# MCISO-S05-V00-CANIsolation.net
KiCad netlist of a schematic drawn in Altium Designer
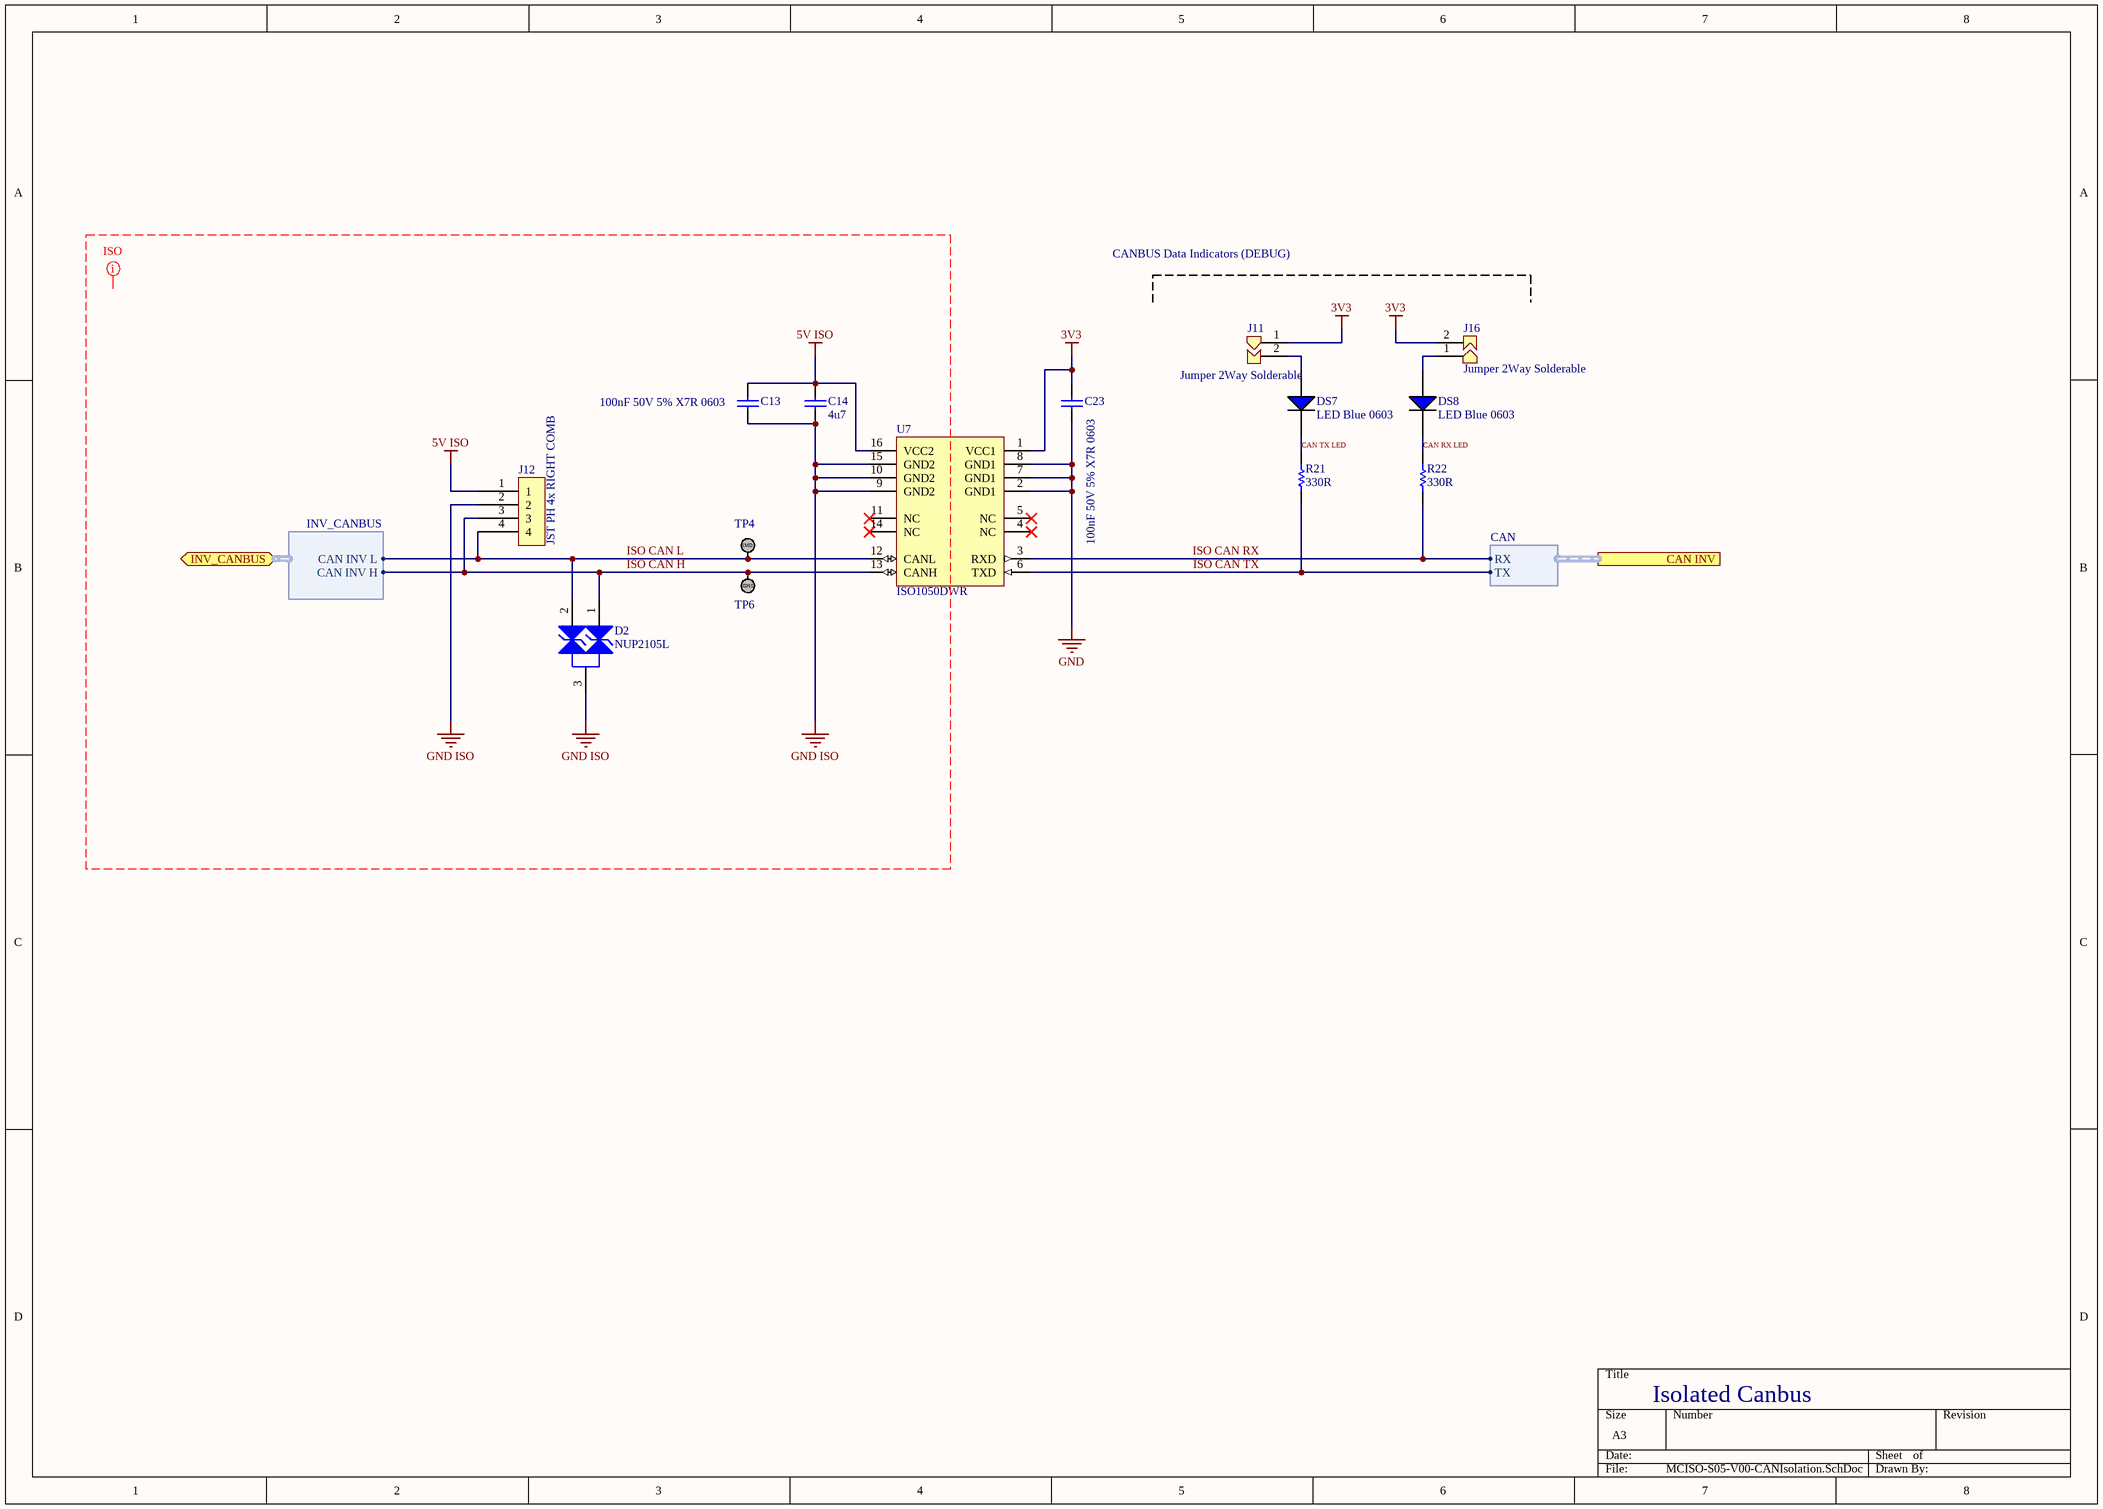
[diagram p0: MCISO-S05-V00-CANIsolation.SchDoc]

(export (version "E")
  (design (tool "Eeschema 10.0.6"))
  (components
    (comp (ref "C13")
      (value "100nF 50V 5% X7R 0603")
      (footprint "Cap_Ceramic_0603")
      (description "Capacitor, Ceramic, SMD, 100nF, 50V, 5%, X7R, 0603")
      (libsource (lib "QUTMS-MCISOLibrary") (part "100nF 50V 5% X7R 0603"))
    )
    (comp (ref "C14")
      (value "4u7")
      (footprint "Cap_Ceramic_0603")
      (description "Capacitor, Ceramic, SMD, 4u7, 50V, 5%, X7R, 0603")
      (libsource (lib "QUTMS-MCISOLibrary") (part "4u7 50V 5% X7R 0603"))
    )
    (comp (ref "C23")
      (value "100nF 50V 5% X7R 0603")
      (footprint "Cap_Ceramic_0603")
      (description "Capacitor, Ceramic, SMD, 100nF, 50V, 5%, X7R, 0603")
      (libsource (lib "QUTMS-MCISOLibrary") (part "100nF 50V 5% X7R 0603"))
    )
    (comp (ref "D2")
      (value "NUP2105L")
      (footprint "NUP2105L")
      (libsource (lib "QUTMS_CANLibrary") (part "NUP2105L"))
    )
    (comp (ref "DS7")
      (value "LED Blue 0603")
      (footprint "LED BLUE 0603")
      (libsource (lib "QUTMS_LEDLibrary") (part "LED BLUE 0603"))
    )
    (comp (ref "DS8")
      (value "LED Blue 0603")
      (footprint "LED BLUE 0603")
      (libsource (lib "QUTMS_LEDLibrary") (part "LED BLUE 0603"))
    )
    (comp (ref "J11")
      (value "Jumper 2Way Solderable")
      (footprint "Jumper_2Way_Solderable")
      (description "Jumper 2Way Side Solderable")
      (libsource (lib "QUTMS_JumperLibrary") (part "Jumper 2Way Side Solderable"))
    )
    (comp (ref "J12")
      (value "JST PH 4x RIGHT COMB")
      (footprint "JST PH 4x RIGHT COMB")
      (description "CAN Ethernet Bridge Port")
      (libsource (lib "QUTMS-MCISOLibrary") (part "JST PH 4x RIGHT COMB"))
    )
    (comp (ref "J16")
      (value "Jumper 2Way Solderable")
      (footprint "Jumper_2Way_Solderable")
      (description "Jumper 2Way Side Solderable")
      (libsource (lib "QUTMS_JumperLibrary") (part "Jumper 2Way Side Solderable"))
    )
    (comp (ref "R21")
      (value "330R")
      (footprint "Res_ThinFilm_0603")
      (description "Resistor, SMD, 330R, 0.1W, 5%, 0603")
      (libsource (lib "StandardResistors") (part "330R 5% 0603"))
    )
    (comp (ref "R22")
      (value "330R")
      (footprint "Res_ThinFilm_0603")
      (description "Resistor, SMD, 330R, 0.1W, 5%, 0603")
      (libsource (lib "StandardResistors") (part "330R 5% 0603"))
    )
    (comp (ref "TP4")
      (value "TestPoint_SMD")
      (footprint "TestPointSMD")
      (libsource (lib "StandardTest") (part "TestPoint_SMD"))
    )
    (comp (ref "TP6")
      (value "TestPoint_SMD")
      (footprint "TestPointSMD")
      (libsource (lib "StandardTest") (part "TestPoint_SMD"))
    )
    (comp (ref "U7")
      (value "ISO1050DWR")
      (footprint "QUTMS-MCISOLibrary:DW00016B_V")
      (description "Isolated CAN Transceiver, -55 to 105 degC, 16-pin SOIC (DW), Green (RoHS & no Sb/Br)")
      (fields (field (name "MANUFACTURER") "Texas Instruments"))
      (libsource (lib "QUTMS-MCISOLibrary") (part "ISO1050DWR"))
    )
  )
  (nets
    (net (code "3") (name "/CAN RX LED") (class "Default")
      (node (ref "DS8") (pin "2") (pinfunction "C_2") (pintype "passive"))
      (node (ref "R22") (pin "2") (pinfunction "2_2") (pintype "passive"))
    )
    (net (code "4") (name "/CAN TX LED") (class "Default")
      (node (ref "DS7") (pin "2") (pinfunction "C_2") (pintype "passive"))
      (node (ref "R21") (pin "2") (pinfunction "2_2") (pintype "passive"))
    )
    (net (code "5") (name "/ISO CAN H") (class "Default")
      (node (ref "D2") (pin "1") (pinfunction "1_1") (pintype "passive"))
      (node (ref "J12") (pin "3") (pinfunction "3_3") (pintype "passive"))
      (node (ref "TP6") (pin "1") (pinfunction "1_1") (pintype "passive"))
      (node (ref "U7") (pin "13") (pinfunction "CANH_13") (pintype "bidirectional"))
    )
    (net (code "6") (name "/ISO CAN L") (class "Default")
      (node (ref "D2") (pin "2") (pinfunction "2_2") (pintype "passive"))
      (node (ref "J12") (pin "4") (pinfunction "4_4") (pintype "passive"))
      (node (ref "TP4") (pin "1") (pinfunction "1_1") (pintype "passive"))
      (node (ref "U7") (pin "12") (pinfunction "CANL_12") (pintype "bidirectional"))
    )
    (net (code "7") (name "/ISO CAN RX") (class "Default")
      (node (ref "R22") (pin "1") (pinfunction "1_1") (pintype "passive"))
      (node (ref "U7") (pin "3") (pinfunction "RXD_3") (pintype "output"))
    )
    (net (code "8") (name "/ISO CAN TX") (class "Default")
      (node (ref "R21") (pin "1") (pinfunction "1_1") (pintype "passive"))
      (node (ref "U7") (pin "6") (pinfunction "TXD_6") (pintype "input"))
    )
    (net (code "11") (name "3V3") (class "Default")
      (node (ref "C23") (pin "2") (pinfunction "2_2") (pintype "passive"))
      (node (ref "J11") (pin "1") (pinfunction "1_1") (pintype "passive"))
      (node (ref "J16") (pin "2") (pinfunction "2_2") (pintype "passive"))
      (node (ref "U7") (pin "1") (pinfunction "VCC1_1") (pintype "power_in"))
    )
    (net (code "12") (name "5V ISO") (class "Default")
      (node (ref "C13") (pin "2") (pinfunction "2_2") (pintype "passive"))
      (node (ref "C14") (pin "2") (pinfunction "2_2") (pintype "passive"))
      (node (ref "J12") (pin "1") (pinfunction "1_1") (pintype "passive"))
      (node (ref "U7") (pin "16") (pinfunction "VCC2_16") (pintype "power_in"))
    )
    (net (code "13") (name "GND") (class "Default")
      (node (ref "C23") (pin "1") (pinfunction "1_1") (pintype "passive"))
      (node (ref "U7") (pin "2") (pinfunction "GND1_2") (pintype "power_in"))
      (node (ref "U7") (pin "7") (pinfunction "GND1_7") (pintype "power_in"))
      (node (ref "U7") (pin "8") (pinfunction "GND1_8") (pintype "power_in"))
    )
    (net (code "14") (name "GND ISO") (class "Default")
      (node (ref "C13") (pin "1") (pinfunction "1_1") (pintype "passive"))
      (node (ref "C14") (pin "1") (pinfunction "1_1") (pintype "passive"))
      (node (ref "D2") (pin "3") (pinfunction "3_3") (pintype "passive"))
      (node (ref "J12") (pin "2") (pinfunction "2_2") (pintype "passive"))
      (node (ref "U7") (pin "10") (pinfunction "GND2_10") (pintype "power_in"))
      (node (ref "U7") (pin "15") (pinfunction "GND2_15") (pintype "power_in"))
      (node (ref "U7") (pin "9") (pinfunction "GND2_9") (pintype "power_in"))
    )
    (net (code "15") (name "Net-(DS7-A)") (class "Default")
      (node (ref "DS7") (pin "1") (pinfunction "A_1") (pintype "passive"))
      (node (ref "J11") (pin "2") (pinfunction "2_2") (pintype "passive"))
    )
    (net (code "16") (name "Net-(DS8-A)") (class "Default")
      (node (ref "DS8") (pin "1") (pinfunction "A_1") (pintype "passive"))
      (node (ref "J16") (pin "1") (pinfunction "1_1") (pintype "passive"))
    )
    (net (code "17") (name "unconnected-(U7-NC-Pad4)") (class "Default")
      (node (ref "U7") (pin "4") (pinfunction "NC_4") (pintype "passive+no_connect"))
    )
    (net (code "18") (name "unconnected-(U7-NC-Pad5)") (class "Default")
      (node (ref "U7") (pin "5") (pinfunction "NC_5") (pintype "passive+no_connect"))
    )
    (net (code "19") (name "unconnected-(U7-NC-Pad11)") (class "Default")
      (node (ref "U7") (pin "11") (pinfunction "NC_11") (pintype "passive+no_connect"))
    )
    (net (code "20") (name "unconnected-(U7-NC-Pad14)") (class "Default")
      (node (ref "U7") (pin "14") (pinfunction "NC_14") (pintype "passive+no_connect"))
    )
  )
)
